# 467444_130_3_3-A.net
KiCad netlist of a schematic drawn in Altium Designer
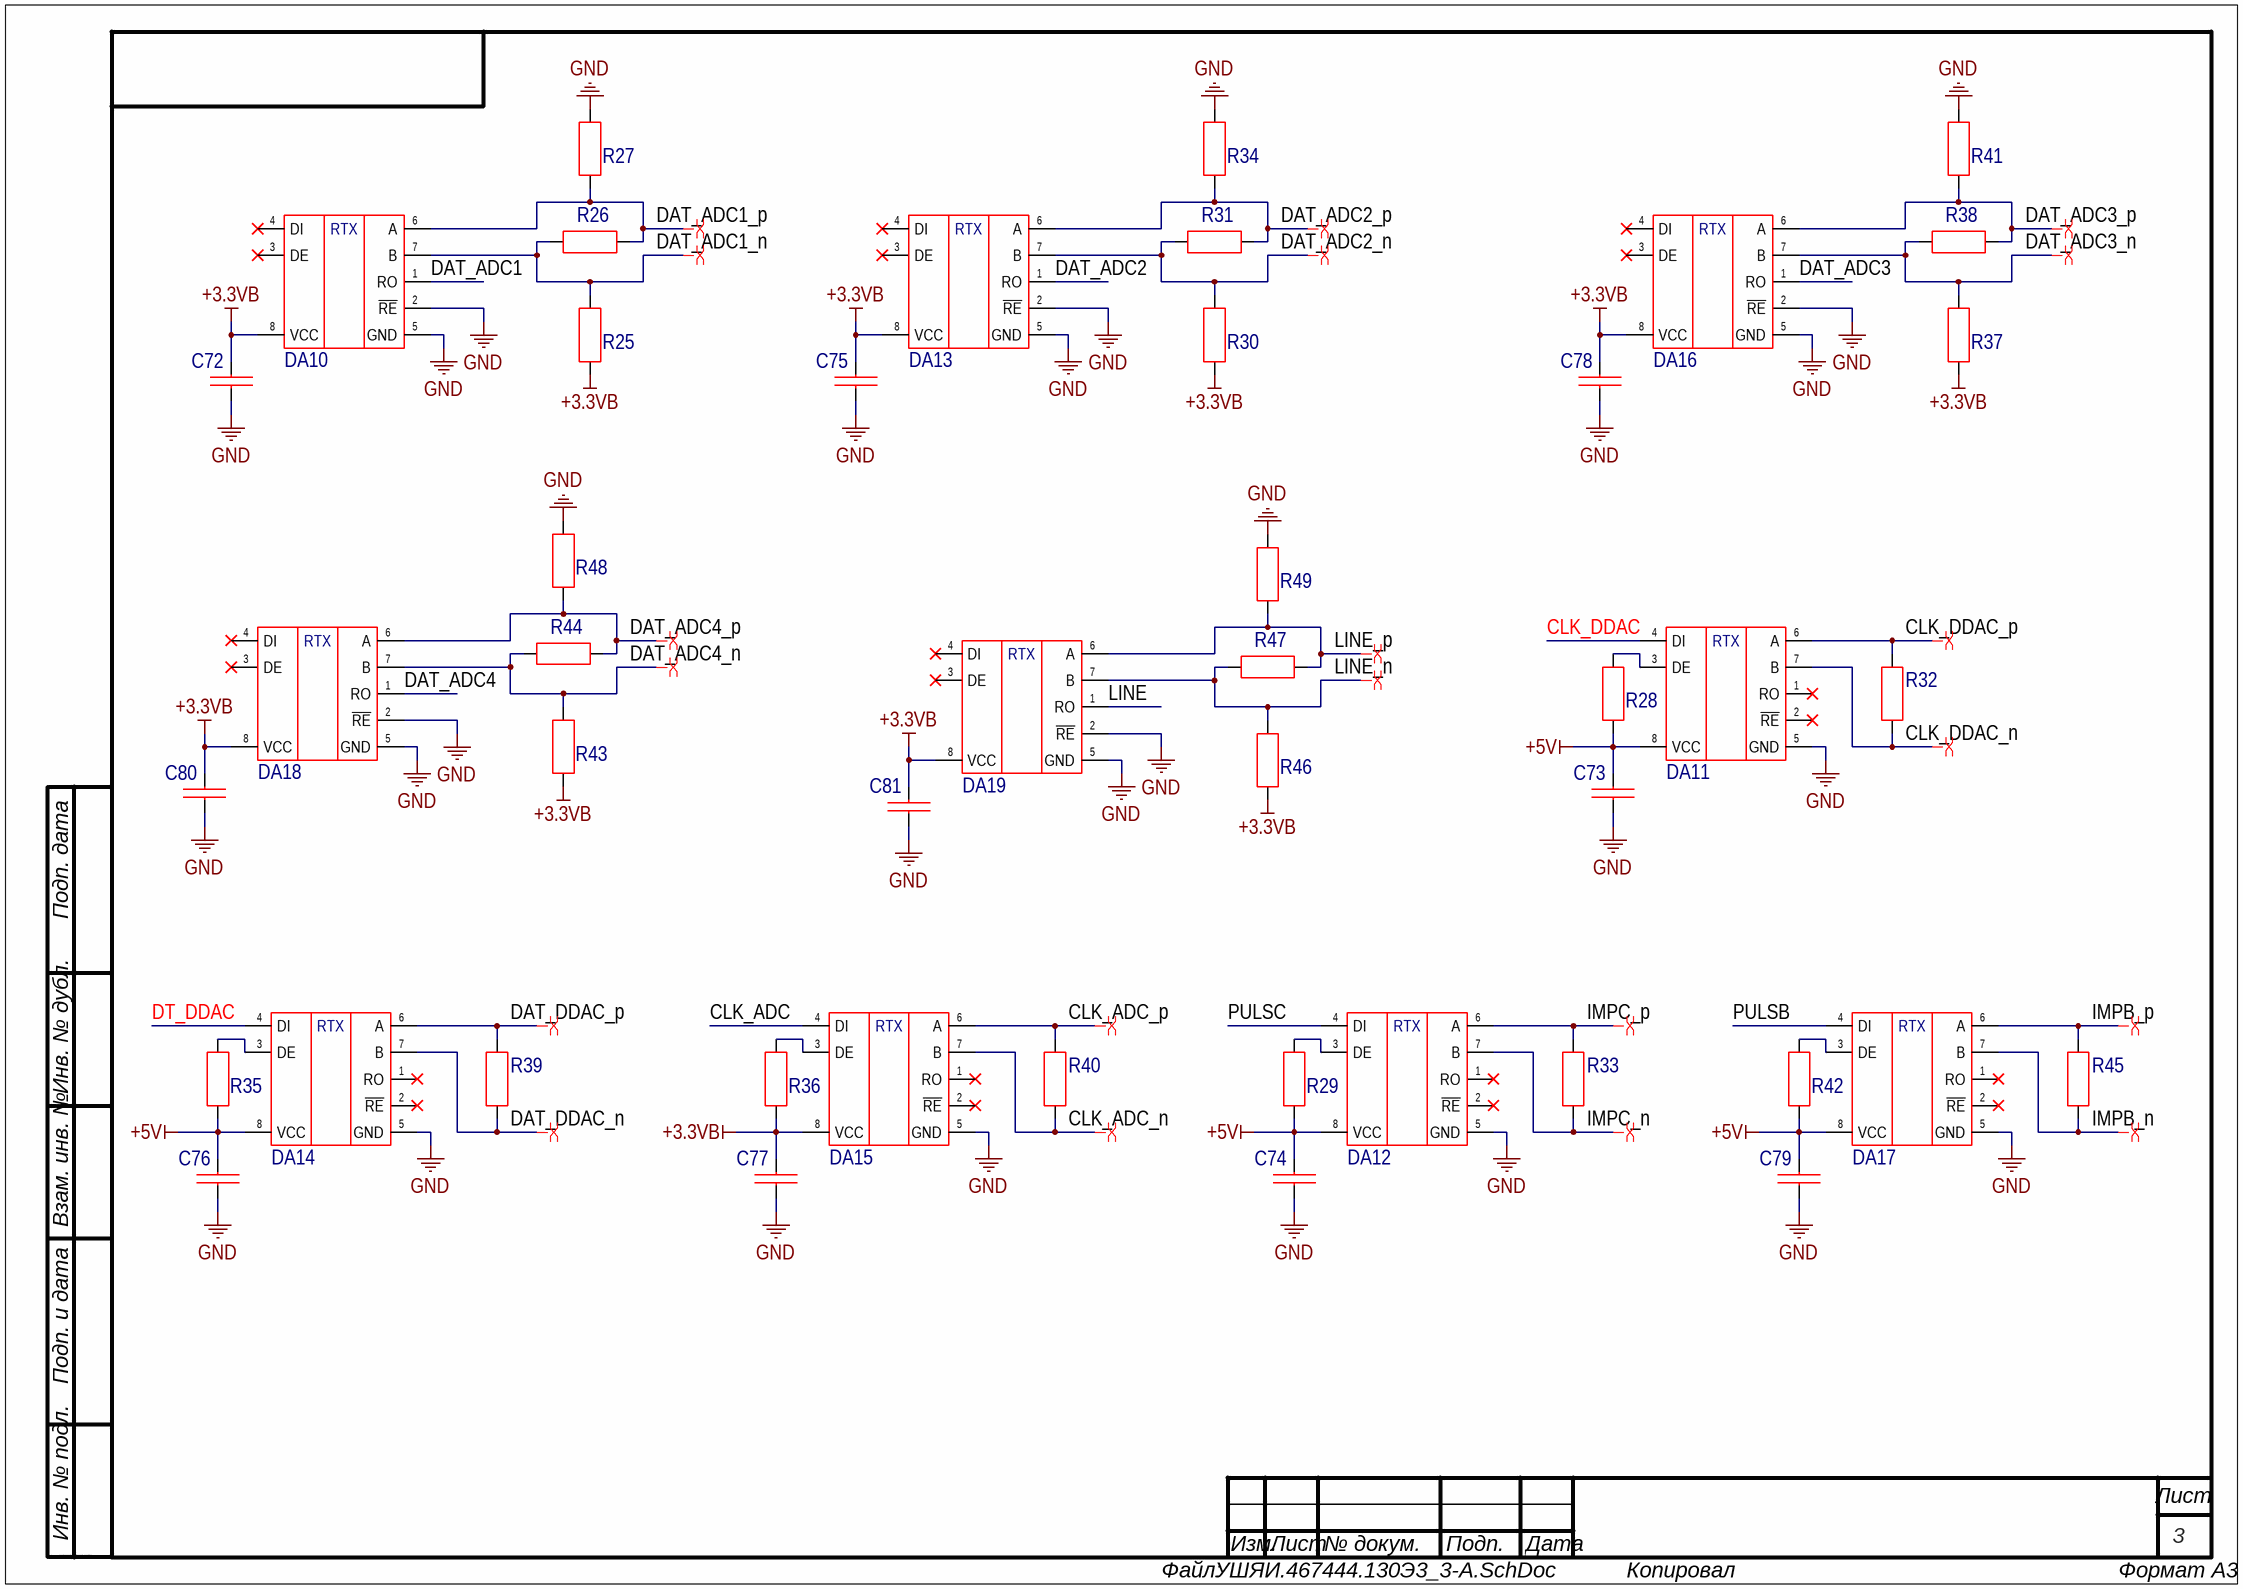
[diagram p0: УШЯИ.467444.130Э3_3-A.SchDoc]

(export (version "E")
  (design (tool "Eeschema 10.0.6"))
  (components
    (comp (ref "C72")
      (value "0,1 µF")
      (footprint "C_0805 [2012 Metric]")
      (description "Неполярный конденсатор")
      (fields (field (name "MANUFACTURER") "Murata") (field (name "VOLTAGE") "50V"))
      (libsource (lib "lib") (part "C_const"))
    )
    (comp (ref "C73")
      (value "0,1 µF")
      (footprint "C_0805 [2012 Metric]")
      (description "Неполярный конденсатор")
      (fields (field (name "MANUFACTURER") "Murata") (field (name "VOLTAGE") "50V"))
      (libsource (lib "lib") (part "C_const"))
    )
    (comp (ref "C74")
      (value "0,1 µF")
      (footprint "C_0805 [2012 Metric]")
      (description "Неполярный конденсатор")
      (fields (field (name "MANUFACTURER") "Murata") (field (name "VOLTAGE") "50V"))
      (libsource (lib "lib") (part "C_const"))
    )
    (comp (ref "C75")
      (value "0,1 µF")
      (footprint "C_0805 [2012 Metric]")
      (description "Неполярный конденсатор")
      (fields (field (name "MANUFACTURER") "Murata") (field (name "VOLTAGE") "50V"))
      (libsource (lib "lib") (part "C_const"))
    )
    (comp (ref "C76")
      (value "0,1 µF")
      (footprint "C_0805 [2012 Metric]")
      (description "Неполярный конденсатор")
      (fields (field (name "MANUFACTURER") "Murata") (field (name "VOLTAGE") "50V"))
      (libsource (lib "lib") (part "C_const"))
    )
    (comp (ref "C77")
      (value "0,1 µF")
      (footprint "C_0805 [2012 Metric]")
      (description "Неполярный конденсатор")
      (fields (field (name "MANUFACTURER") "Murata") (field (name "VOLTAGE") "50V"))
      (libsource (lib "lib") (part "C_const"))
    )
    (comp (ref "C78")
      (value "0,1 µF")
      (footprint "C_0805 [2012 Metric]")
      (description "Неполярный конденсатор")
      (fields (field (name "MANUFACTURER") "Murata") (field (name "VOLTAGE") "50V"))
      (libsource (lib "lib") (part "C_const"))
    )
    (comp (ref "C79")
      (value "0,1 µF")
      (footprint "C_0805 [2012 Metric]")
      (description "Неполярный конденсатор")
      (fields (field (name "MANUFACTURER") "Murata") (field (name "VOLTAGE") "50V"))
      (libsource (lib "lib") (part "C_const"))
    )
    (comp (ref "C80")
      (value "0,1 µF")
      (footprint "C_0805 [2012 Metric]")
      (description "Неполярный конденсатор")
      (fields (field (name "MANUFACTURER") "Murata") (field (name "VOLTAGE") "50V"))
      (libsource (lib "lib") (part "C_const"))
    )
    (comp (ref "C81")
      (value "0,1 µF")
      (footprint "C_0805 [2012 Metric]")
      (description "Неполярный конденсатор")
      (fields (field (name "MANUFACTURER") "Murata") (field (name "VOLTAGE") "50V"))
      (libsource (lib "lib") (part "C_const"))
    )
    (comp (ref "DA10")
      (value "SN65HVD75D")
      (footprint "SOIC-8_1.27_5x4x1.75")
      (description "IC, RS422 / RS485 Transceiver IC, 1 Driver, 1 Receiver, 3 V to 3.6 V, -40°C to 125°C, SOIC-8")
      (fields (field (name "MANUFACTURER") "Texas Instruments"))
      (libsource (lib "lib") (part "ADM483"))
    )
    (comp (ref "DA11")
      (value "ADM483AR")
      (footprint "SOIC-8_1.27_5x4x1.75")
      (description "IC, Transceiver, RS422/RS485, 1 Driver, 1 Receiver, 4.75 V to 5.25 V, -40°C to 125°C")
      (fields (field (name "MANUFACTURER") "Analog Devices"))
      (libsource (lib "lib") (part "ADM483"))
    )
    (comp (ref "DA12")
      (value "ADM483AR")
      (footprint "SOIC-8_1.27_5x4x1.75")
      (description "IC, Transceiver, RS422/RS485, 1 Driver, 1 Receiver, 4.75 V to 5.25 V, -40°C to 125°C")
      (fields (field (name "MANUFACTURER") "Analog Devices"))
      (libsource (lib "lib") (part "ADM483"))
    )
    (comp (ref "DA13")
      (value "SN65HVD75D")
      (footprint "SOIC-8_1.27_5x4x1.75")
      (description "IC, RS422 / RS485 Transceiver IC, 1 Driver, 1 Receiver, 3 V to 3.6 V, -40°C to 125°C, SOIC-8")
      (fields (field (name "MANUFACTURER") "Texas Instruments"))
      (libsource (lib "lib") (part "ADM483"))
    )
    (comp (ref "DA14")
      (value "ADM483AR")
      (footprint "SOIC-8_1.27_5x4x1.75")
      (description "IC, Transceiver, RS422/RS485, 1 Driver, 1 Receiver, 4.75 V to 5.25 V, -40°C to 125°C")
      (fields (field (name "MANUFACTURER") "Analog Devices"))
      (libsource (lib "lib") (part "ADM483"))
    )
    (comp (ref "DA15")
      (value "SN65HVD75D")
      (footprint "SOIC-8_1.27_5x4x1.75")
      (description "IC, RS422 / RS485 Transceiver IC, 1 Driver, 1 Receiver, 3 V to 3.6 V, -40°C to 125°C, SOIC-8")
      (fields (field (name "MANUFACTURER") "Texas Instruments"))
      (libsource (lib "lib") (part "ADM483"))
    )
    (comp (ref "DA16")
      (value "SN65HVD75D")
      (footprint "SOIC-8_1.27_5x4x1.75")
      (description "IC, RS422 / RS485 Transceiver IC, 1 Driver, 1 Receiver, 3 V to 3.6 V, -40°C to 125°C, SOIC-8")
      (fields (field (name "MANUFACTURER") "Texas Instruments"))
      (libsource (lib "lib") (part "ADM483"))
    )
    (comp (ref "DA17")
      (value "ADM483AR")
      (footprint "SOIC-8_1.27_5x4x1.75")
      (description "IC, Transceiver, RS422/RS485, 1 Driver, 1 Receiver, 4.75 V to 5.25 V, -40°C to 125°C")
      (fields (field (name "MANUFACTURER") "Analog Devices"))
      (libsource (lib "lib") (part "ADM483"))
    )
    (comp (ref "DA18")
      (value "SN65HVD75D")
      (footprint "SOIC-8_1.27_5x4x1.75")
      (description "IC, RS422 / RS485 Transceiver IC, 1 Driver, 1 Receiver, 3 V to 3.6 V, -40°C to 125°C, SOIC-8")
      (fields (field (name "MANUFACTURER") "Texas Instruments"))
      (libsource (lib "lib") (part "ADM483"))
    )
    (comp (ref "DA19")
      (value "SN65HVD75D")
      (footprint "SOIC-8_1.27_5x4x1.75")
      (description "IC, RS422 / RS485 Transceiver IC, 1 Driver, 1 Receiver, 3 V to 3.6 V, -40°C to 125°C, SOIC-8")
      (fields (field (name "MANUFACTURER") "Texas Instruments"))
      (libsource (lib "lib") (part "ADM483"))
    )
    (comp (ref "R25")
      (value "1k")
      (footprint "R_1206 [3216 Metric]")
      (fields (field (name "TOLERANCE") "±5%"))
      (libsource (lib "lib") (part "R_Const"))
    )
    (comp (ref "R26")
      (value "100R")
      (footprint "R_0805 [2012 Metric]")
      (fields (field (name "TOLERANCE") "±5%"))
      (libsource (lib "lib") (part "R_Const"))
    )
    (comp (ref "R27")
      (value "1k")
      (footprint "R_1206 [3216 Metric]")
      (fields (field (name "TOLERANCE") "±5%"))
      (libsource (lib "lib") (part "R_Const"))
    )
    (comp (ref "R28")
      (value "10k")
      (footprint "R_0805 [2012 Metric]")
      (fields (field (name "TOLERANCE") "±5%"))
      (libsource (lib "lib") (part "R_Const"))
    )
    (comp (ref "R29")
      (value "10k")
      (footprint "R_0805 [2012 Metric]")
      (fields (field (name "TOLERANCE") "±5%"))
      (libsource (lib "lib") (part "R_Const"))
    )
    (comp (ref "R30")
      (value "100R")
      (footprint "R_0805 [2012 Metric]")
      (fields (field (name "TOLERANCE") "±5%"))
      (libsource (lib "lib") (part "R_Const"))
    )
    (comp (ref "R31")
      (value "100R")
      (footprint "R_0805 [2012 Metric]")
      (fields (field (name "TOLERANCE") "±5%"))
      (libsource (lib "lib") (part "R_Const"))
    )
    (comp (ref "R32")
      (value "100R")
      (footprint "R_0805 [2012 Metric]")
      (fields (field (name "TOLERANCE") "±5%"))
      (libsource (lib "lib") (part "R_Const"))
    )
    (comp (ref "R33")
      (value "100R")
      (footprint "R_0805 [2012 Metric]")
      (fields (field (name "TOLERANCE") "±5%"))
      (libsource (lib "lib") (part "R_Const"))
    )
    (comp (ref "R34")
      (value "1k")
      (footprint "R_1206 [3216 Metric]")
      (fields (field (name "TOLERANCE") "±5%"))
      (libsource (lib "lib") (part "R_Const"))
    )
    (comp (ref "R35")
      (value "10k")
      (footprint "R_0805 [2012 Metric]")
      (fields (field (name "TOLERANCE") "±5%"))
      (libsource (lib "lib") (part "R_Const"))
    )
    (comp (ref "R36")
      (value "10k")
      (footprint "R_0805 [2012 Metric]")
      (fields (field (name "TOLERANCE") "±5%"))
      (libsource (lib "lib") (part "R_Const"))
    )
    (comp (ref "R37")
      (value "1k")
      (footprint "R_1206 [3216 Metric]")
      (fields (field (name "TOLERANCE") "±5%"))
      (libsource (lib "lib") (part "R_Const"))
    )
    (comp (ref "R38")
      (value "100R")
      (footprint "R_0805 [2012 Metric]")
      (fields (field (name "TOLERANCE") "±5%"))
      (libsource (lib "lib") (part "R_Const"))
    )
    (comp (ref "R39")
      (value "100R")
      (footprint "R_0805 [2012 Metric]")
      (fields (field (name "TOLERANCE") "±5%"))
      (libsource (lib "lib") (part "R_Const"))
    )
    (comp (ref "R40")
      (value "100R")
      (footprint "R_0805 [2012 Metric]")
      (fields (field (name "TOLERANCE") "±5%"))
      (libsource (lib "lib") (part "R_Const"))
    )
    (comp (ref "R41")
      (value "1k")
      (footprint "R_1206 [3216 Metric]")
      (fields (field (name "TOLERANCE") "±5%"))
      (libsource (lib "lib") (part "R_Const"))
    )
    (comp (ref "R42")
      (value "10k")
      (footprint "R_0805 [2012 Metric]")
      (fields (field (name "TOLERANCE") "±5%"))
      (libsource (lib "lib") (part "R_Const"))
    )
    (comp (ref "R43")
      (value "1k")
      (footprint "R_1206 [3216 Metric]")
      (fields (field (name "TOLERANCE") "±5%"))
      (libsource (lib "lib") (part "R_Const"))
    )
    (comp (ref "R44")
      (value "100R")
      (footprint "R_0805 [2012 Metric]")
      (fields (field (name "TOLERANCE") "±5%"))
      (libsource (lib "lib") (part "R_Const"))
    )
    (comp (ref "R45")
      (value "100R")
      (footprint "R_0805 [2012 Metric]")
      (fields (field (name "TOLERANCE") "±5%"))
      (libsource (lib "lib") (part "R_Const"))
    )
    (comp (ref "R46")
      (value "1k")
      (footprint "R_1206 [3216 Metric]")
      (fields (field (name "TOLERANCE") "±5%"))
      (libsource (lib "lib") (part "R_Const"))
    )
    (comp (ref "R47")
      (value "100R")
      (footprint "R_0805 [2012 Metric]")
      (fields (field (name "TOLERANCE") "±5%"))
      (libsource (lib "lib") (part "R_Const"))
    )
    (comp (ref "R48")
      (value "1k")
      (footprint "R_1206 [3216 Metric]")
      (fields (field (name "TOLERANCE") "±5%"))
      (libsource (lib "lib") (part "R_Const"))
    )
    (comp (ref "R49")
      (value "1k")
      (footprint "R_1206 [3216 Metric]")
      (fields (field (name "TOLERANCE") "±5%"))
      (libsource (lib "lib") (part "R_Const"))
    )
  )
  (nets
    (net (code "1") (name "+3.3VB") (class "Default")
      (node (ref "C72") (pin "2") (pinfunction "2_2") (pintype "passive"))
      (node (ref "C75") (pin "2") (pinfunction "2_2") (pintype "passive"))
      (node (ref "C77") (pin "2") (pinfunction "2_2") (pintype "passive"))
      (node (ref "C78") (pin "2") (pinfunction "2_2") (pintype "passive"))
      (node (ref "C80") (pin "2") (pinfunction "2_2") (pintype "passive"))
      (node (ref "C81") (pin "2") (pinfunction "2_2") (pintype "passive"))
      (node (ref "DA10") (pin "8") (pinfunction "VCC_8") (pintype "passive"))
      (node (ref "DA13") (pin "8") (pinfunction "VCC_8") (pintype "passive"))
      (node (ref "DA15") (pin "8") (pinfunction "VCC_8") (pintype "passive"))
      (node (ref "DA16") (pin "8") (pinfunction "VCC_8") (pintype "passive"))
      (node (ref "DA18") (pin "8") (pinfunction "VCC_8") (pintype "passive"))
      (node (ref "DA19") (pin "8") (pinfunction "VCC_8") (pintype "passive"))
      (node (ref "R25") (pin "1") (pinfunction "1_1") (pintype "passive"))
      (node (ref "R30") (pin "1") (pinfunction "1_1") (pintype "passive"))
      (node (ref "R36") (pin "1") (pinfunction "1_1") (pintype "passive"))
      (node (ref "R37") (pin "1") (pinfunction "1_1") (pintype "passive"))
      (node (ref "R43") (pin "1") (pinfunction "1_1") (pintype "passive"))
      (node (ref "R46") (pin "1") (pinfunction "1_1") (pintype "passive"))
    )
    (net (code "2") (name "+5V") (class "Default")
      (node (ref "C73") (pin "2") (pinfunction "2_2") (pintype "passive"))
      (node (ref "C74") (pin "2") (pinfunction "2_2") (pintype "passive"))
      (node (ref "C76") (pin "2") (pinfunction "2_2") (pintype "passive"))
      (node (ref "C79") (pin "2") (pinfunction "2_2") (pintype "passive"))
      (node (ref "DA11") (pin "8") (pinfunction "VCC_8") (pintype "passive"))
      (node (ref "DA12") (pin "8") (pinfunction "VCC_8") (pintype "passive"))
      (node (ref "DA14") (pin "8") (pinfunction "VCC_8") (pintype "passive"))
      (node (ref "DA17") (pin "8") (pinfunction "VCC_8") (pintype "passive"))
      (node (ref "R28") (pin "1") (pinfunction "1_1") (pintype "passive"))
      (node (ref "R29") (pin "1") (pinfunction "1_1") (pintype "passive"))
      (node (ref "R35") (pin "1") (pinfunction "1_1") (pintype "passive"))
      (node (ref "R42") (pin "1") (pinfunction "1_1") (pintype "passive"))
    )
    (net (code "3") (name "/CLK_ADC") (class "Default")
      (node (ref "DA15") (pin "4") (pinfunction "DI_4") (pintype "passive"))
    )
    (net (code "4") (name "/CLK_ADC_n") (class "Default")
      (node (ref "DA15") (pin "7") (pinfunction "B_7") (pintype "passive"))
      (node (ref "R40") (pin "1") (pinfunction "1_1") (pintype "passive"))
    )
    (net (code "5") (name "/CLK_ADC_p") (class "Default")
      (node (ref "DA15") (pin "6") (pinfunction "A_6") (pintype "passive"))
      (node (ref "R40") (pin "2") (pinfunction "2_2") (pintype "passive"))
    )
    (net (code "6") (name "/CLK_DDAC") (class "Default")
      (node (ref "DA11") (pin "4") (pinfunction "DI_4") (pintype "passive"))
    )
    (net (code "7") (name "/CLK_DDAC_n") (class "Default")
      (node (ref "DA11") (pin "7") (pinfunction "B_7") (pintype "passive"))
      (node (ref "R32") (pin "1") (pinfunction "1_1") (pintype "passive"))
    )
    (net (code "8") (name "/CLK_DDAC_p") (class "Default")
      (node (ref "DA11") (pin "6") (pinfunction "A_6") (pintype "passive"))
      (node (ref "R32") (pin "2") (pinfunction "2_2") (pintype "passive"))
    )
    (net (code "9") (name "/DAT_ADC1") (class "Default")
      (node (ref "DA10") (pin "1") (pinfunction "RO_1") (pintype "passive"))
    )
    (net (code "10") (name "/DAT_ADC1_n") (class "Default")
      (node (ref "DA10") (pin "7") (pinfunction "B_7") (pintype "passive"))
      (node (ref "R25") (pin "2") (pinfunction "2_2") (pintype "passive"))
      (node (ref "R26") (pin "1") (pinfunction "1_1") (pintype "passive"))
    )
    (net (code "11") (name "/DAT_ADC1_p") (class "Default")
      (node (ref "DA10") (pin "6") (pinfunction "A_6") (pintype "passive"))
      (node (ref "R26") (pin "2") (pinfunction "2_2") (pintype "passive"))
      (node (ref "R27") (pin "1") (pinfunction "1_1") (pintype "passive"))
    )
    (net (code "12") (name "/DAT_ADC2") (class "Default")
      (node (ref "DA13") (pin "1") (pinfunction "RO_1") (pintype "passive"))
    )
    (net (code "13") (name "/DAT_ADC2_n") (class "Default")
      (node (ref "DA13") (pin "7") (pinfunction "B_7") (pintype "passive"))
      (node (ref "R30") (pin "2") (pinfunction "2_2") (pintype "passive"))
      (node (ref "R31") (pin "1") (pinfunction "1_1") (pintype "passive"))
    )
    (net (code "14") (name "/DAT_ADC2_p") (class "Default")
      (node (ref "DA13") (pin "6") (pinfunction "A_6") (pintype "passive"))
      (node (ref "R31") (pin "2") (pinfunction "2_2") (pintype "passive"))
      (node (ref "R34") (pin "1") (pinfunction "1_1") (pintype "passive"))
    )
    (net (code "15") (name "/DAT_ADC3") (class "Default")
      (node (ref "DA16") (pin "1") (pinfunction "RO_1") (pintype "passive"))
    )
    (net (code "16") (name "/DAT_ADC3_n") (class "Default")
      (node (ref "DA16") (pin "7") (pinfunction "B_7") (pintype "passive"))
      (node (ref "R37") (pin "2") (pinfunction "2_2") (pintype "passive"))
      (node (ref "R38") (pin "1") (pinfunction "1_1") (pintype "passive"))
    )
    (net (code "17") (name "/DAT_ADC3_p") (class "Default")
      (node (ref "DA16") (pin "6") (pinfunction "A_6") (pintype "passive"))
      (node (ref "R38") (pin "2") (pinfunction "2_2") (pintype "passive"))
      (node (ref "R41") (pin "1") (pinfunction "1_1") (pintype "passive"))
    )
    (net (code "18") (name "/DAT_ADC4") (class "Default")
      (node (ref "DA18") (pin "1") (pinfunction "RO_1") (pintype "passive"))
    )
    (net (code "19") (name "/DAT_ADC4_n") (class "Default")
      (node (ref "DA18") (pin "7") (pinfunction "B_7") (pintype "passive"))
      (node (ref "R43") (pin "2") (pinfunction "2_2") (pintype "passive"))
      (node (ref "R44") (pin "1") (pinfunction "1_1") (pintype "passive"))
    )
    (net (code "20") (name "/DAT_ADC4_p") (class "Default")
      (node (ref "DA18") (pin "6") (pinfunction "A_6") (pintype "passive"))
      (node (ref "R44") (pin "2") (pinfunction "2_2") (pintype "passive"))
      (node (ref "R48") (pin "1") (pinfunction "1_1") (pintype "passive"))
    )
    (net (code "21") (name "/DAT_DDAC_n") (class "Default")
      (node (ref "DA14") (pin "7") (pinfunction "B_7") (pintype "passive"))
      (node (ref "R39") (pin "1") (pinfunction "1_1") (pintype "passive"))
    )
    (net (code "22") (name "/DAT_DDAC_p") (class "Default")
      (node (ref "DA14") (pin "6") (pinfunction "A_6") (pintype "passive"))
      (node (ref "R39") (pin "2") (pinfunction "2_2") (pintype "passive"))
    )
    (net (code "23") (name "/DT_DDAC") (class "Default")
      (node (ref "DA14") (pin "4") (pinfunction "DI_4") (pintype "passive"))
    )
    (net (code "24") (name "/IMPB_n") (class "Default")
      (node (ref "DA17") (pin "7") (pinfunction "B_7") (pintype "passive"))
      (node (ref "R45") (pin "1") (pinfunction "1_1") (pintype "passive"))
    )
    (net (code "25") (name "/IMPB_p") (class "Default")
      (node (ref "DA17") (pin "6") (pinfunction "A_6") (pintype "passive"))
      (node (ref "R45") (pin "2") (pinfunction "2_2") (pintype "passive"))
    )
    (net (code "26") (name "/IMPC_n") (class "Default")
      (node (ref "DA12") (pin "7") (pinfunction "B_7") (pintype "passive"))
      (node (ref "R33") (pin "1") (pinfunction "1_1") (pintype "passive"))
    )
    (net (code "27") (name "/IMPC_p") (class "Default")
      (node (ref "DA12") (pin "6") (pinfunction "A_6") (pintype "passive"))
      (node (ref "R33") (pin "2") (pinfunction "2_2") (pintype "passive"))
    )
    (net (code "28") (name "/LINE") (class "Default")
      (node (ref "DA19") (pin "1") (pinfunction "RO_1") (pintype "passive"))
    )
    (net (code "29") (name "/LINE_n") (class "Default")
      (node (ref "DA19") (pin "7") (pinfunction "B_7") (pintype "passive"))
      (node (ref "R46") (pin "2") (pinfunction "2_2") (pintype "passive"))
      (node (ref "R47") (pin "1") (pinfunction "1_1") (pintype "passive"))
    )
    (net (code "30") (name "/LINE_p") (class "Default")
      (node (ref "DA19") (pin "6") (pinfunction "A_6") (pintype "passive"))
      (node (ref "R47") (pin "2") (pinfunction "2_2") (pintype "passive"))
      (node (ref "R49") (pin "1") (pinfunction "1_1") (pintype "passive"))
    )
    (net (code "31") (name "/PULSB") (class "Default")
      (node (ref "DA17") (pin "4") (pinfunction "DI_4") (pintype "passive"))
    )
    (net (code "32") (name "/PULSC") (class "Default")
      (node (ref "DA12") (pin "4") (pinfunction "DI_4") (pintype "passive"))
    )
    (net (code "33") (name "GND") (class "Default")
      (node (ref "C72") (pin "1") (pinfunction "1_1") (pintype "passive"))
      (node (ref "C73") (pin "1") (pinfunction "1_1") (pintype "passive"))
      (node (ref "C74") (pin "1") (pinfunction "1_1") (pintype "passive"))
      (node (ref "C75") (pin "1") (pinfunction "1_1") (pintype "passive"))
      (node (ref "C76") (pin "1") (pinfunction "1_1") (pintype "passive"))
      (node (ref "C77") (pin "1") (pinfunction "1_1") (pintype "passive"))
      (node (ref "C78") (pin "1") (pinfunction "1_1") (pintype "passive"))
      (node (ref "C79") (pin "1") (pinfunction "1_1") (pintype "passive"))
      (node (ref "C80") (pin "1") (pinfunction "1_1") (pintype "passive"))
      (node (ref "C81") (pin "1") (pinfunction "1_1") (pintype "passive"))
      (node (ref "DA10") (pin "2") (pinfunction "~{RE}_2") (pintype "passive"))
      (node (ref "DA10") (pin "5") (pinfunction "GND_5") (pintype "passive"))
      (node (ref "DA11") (pin "5") (pinfunction "GND_5") (pintype "passive"))
      (node (ref "DA12") (pin "5") (pinfunction "GND_5") (pintype "passive"))
      (node (ref "DA13") (pin "2") (pinfunction "~{RE}_2") (pintype "passive"))
      (node (ref "DA13") (pin "5") (pinfunction "GND_5") (pintype "passive"))
      (node (ref "DA14") (pin "5") (pinfunction "GND_5") (pintype "passive"))
      (node (ref "DA15") (pin "5") (pinfunction "GND_5") (pintype "passive"))
      (node (ref "DA16") (pin "2") (pinfunction "~{RE}_2") (pintype "passive"))
      (node (ref "DA16") (pin "5") (pinfunction "GND_5") (pintype "passive"))
      (node (ref "DA17") (pin "5") (pinfunction "GND_5") (pintype "passive"))
      (node (ref "DA18") (pin "2") (pinfunction "~{RE}_2") (pintype "passive"))
      (node (ref "DA18") (pin "5") (pinfunction "GND_5") (pintype "passive"))
      (node (ref "DA19") (pin "2") (pinfunction "~{RE}_2") (pintype "passive"))
      (node (ref "DA19") (pin "5") (pinfunction "GND_5") (pintype "passive"))
      (node (ref "R27") (pin "2") (pinfunction "2_2") (pintype "passive"))
      (node (ref "R34") (pin "2") (pinfunction "2_2") (pintype "passive"))
      (node (ref "R41") (pin "2") (pinfunction "2_2") (pintype "passive"))
      (node (ref "R48") (pin "2") (pinfunction "2_2") (pintype "passive"))
      (node (ref "R49") (pin "2") (pinfunction "2_2") (pintype "passive"))
    )
    (net (code "34") (name "Net-(DA11-DE)") (class "Default")
      (node (ref "DA11") (pin "3") (pinfunction "DE_3") (pintype "passive"))
      (node (ref "R28") (pin "2") (pinfunction "2_2") (pintype "passive"))
    )
    (net (code "35") (name "Net-(DA12-DE)") (class "Default")
      (node (ref "DA12") (pin "3") (pinfunction "DE_3") (pintype "passive"))
      (node (ref "R29") (pin "2") (pinfunction "2_2") (pintype "passive"))
    )
    (net (code "36") (name "Net-(DA14-DE)") (class "Default")
      (node (ref "DA14") (pin "3") (pinfunction "DE_3") (pintype "passive"))
      (node (ref "R35") (pin "2") (pinfunction "2_2") (pintype "passive"))
    )
    (net (code "37") (name "Net-(DA15-DE)") (class "Default")
      (node (ref "DA15") (pin "3") (pinfunction "DE_3") (pintype "passive"))
      (node (ref "R36") (pin "2") (pinfunction "2_2") (pintype "passive"))
    )
    (net (code "38") (name "Net-(DA17-DE)") (class "Default")
      (node (ref "DA17") (pin "3") (pinfunction "DE_3") (pintype "passive"))
      (node (ref "R42") (pin "2") (pinfunction "2_2") (pintype "passive"))
    )
    (net (code "39") (name "unconnected-(DA10-DE-Pad3)") (class "Default")
      (node (ref "DA10") (pin "3") (pinfunction "DE_3") (pintype "passive+no_connect"))
    )
    (net (code "40") (name "unconnected-(DA10-DI-Pad4)") (class "Default")
      (node (ref "DA10") (pin "4") (pinfunction "DI_4") (pintype "passive+no_connect"))
    )
    (net (code "41") (name "unconnected-(DA11-RO-Pad1)") (class "Default")
      (node (ref "DA11") (pin "1") (pinfunction "RO_1") (pintype "passive+no_connect"))
    )
    (net (code "42") (name "unconnected-(DA11-~{RE}-Pad2)") (class "Default")
      (node (ref "DA11") (pin "2") (pinfunction "~{RE}_2") (pintype "passive+no_connect"))
    )
    (net (code "43") (name "unconnected-(DA12-RO-Pad1)") (class "Default")
      (node (ref "DA12") (pin "1") (pinfunction "RO_1") (pintype "passive+no_connect"))
    )
    (net (code "44") (name "unconnected-(DA12-~{RE}-Pad2)") (class "Default")
      (node (ref "DA12") (pin "2") (pinfunction "~{RE}_2") (pintype "passive+no_connect"))
    )
    (net (code "45") (name "unconnected-(DA13-DE-Pad3)") (class "Default")
      (node (ref "DA13") (pin "3") (pinfunction "DE_3") (pintype "passive+no_connect"))
    )
    (net (code "46") (name "unconnected-(DA13-DI-Pad4)") (class "Default")
      (node (ref "DA13") (pin "4") (pinfunction "DI_4") (pintype "passive+no_connect"))
    )
    (net (code "47") (name "unconnected-(DA14-RO-Pad1)") (class "Default")
      (node (ref "DA14") (pin "1") (pinfunction "RO_1") (pintype "passive+no_connect"))
    )
    (net (code "48") (name "unconnected-(DA14-~{RE}-Pad2)") (class "Default")
      (node (ref "DA14") (pin "2") (pinfunction "~{RE}_2") (pintype "passive+no_connect"))
    )
    (net (code "49") (name "unconnected-(DA15-RO-Pad1)") (class "Default")
      (node (ref "DA15") (pin "1") (pinfunction "RO_1") (pintype "passive+no_connect"))
    )
    (net (code "50") (name "unconnected-(DA15-~{RE}-Pad2)") (class "Default")
      (node (ref "DA15") (pin "2") (pinfunction "~{RE}_2") (pintype "passive+no_connect"))
    )
    (net (code "51") (name "unconnected-(DA16-DE-Pad3)") (class "Default")
      (node (ref "DA16") (pin "3") (pinfunction "DE_3") (pintype "passive+no_connect"))
    )
    (net (code "52") (name "unconnected-(DA16-DI-Pad4)") (class "Default")
      (node (ref "DA16") (pin "4") (pinfunction "DI_4") (pintype "passive+no_connect"))
    )
    (net (code "53") (name "unconnected-(DA17-RO-Pad1)") (class "Default")
      (node (ref "DA17") (pin "1") (pinfunction "RO_1") (pintype "passive+no_connect"))
    )
    (net (code "54") (name "unconnected-(DA17-~{RE}-Pad2)") (class "Default")
      (node (ref "DA17") (pin "2") (pinfunction "~{RE}_2") (pintype "passive+no_connect"))
    )
    (net (code "55") (name "unconnected-(DA18-DE-Pad3)") (class "Default")
      (node (ref "DA18") (pin "3") (pinfunction "DE_3") (pintype "passive+no_connect"))
    )
    (net (code "56") (name "unconnected-(DA18-DI-Pad4)") (class "Default")
      (node (ref "DA18") (pin "4") (pinfunction "DI_4") (pintype "passive+no_connect"))
    )
    (net (code "57") (name "unconnected-(DA19-DE-Pad3)") (class "Default")
      (node (ref "DA19") (pin "3") (pinfunction "DE_3") (pintype "passive+no_connect"))
    )
    (net (code "58") (name "unconnected-(DA19-DI-Pad4)") (class "Default")
      (node (ref "DA19") (pin "4") (pinfunction "DI_4") (pintype "passive+no_connect"))
    )
  )
)
